# Motor_Driver_Unit_MDU.net
KiCad netlist of a schematic drawn in Altium Designer
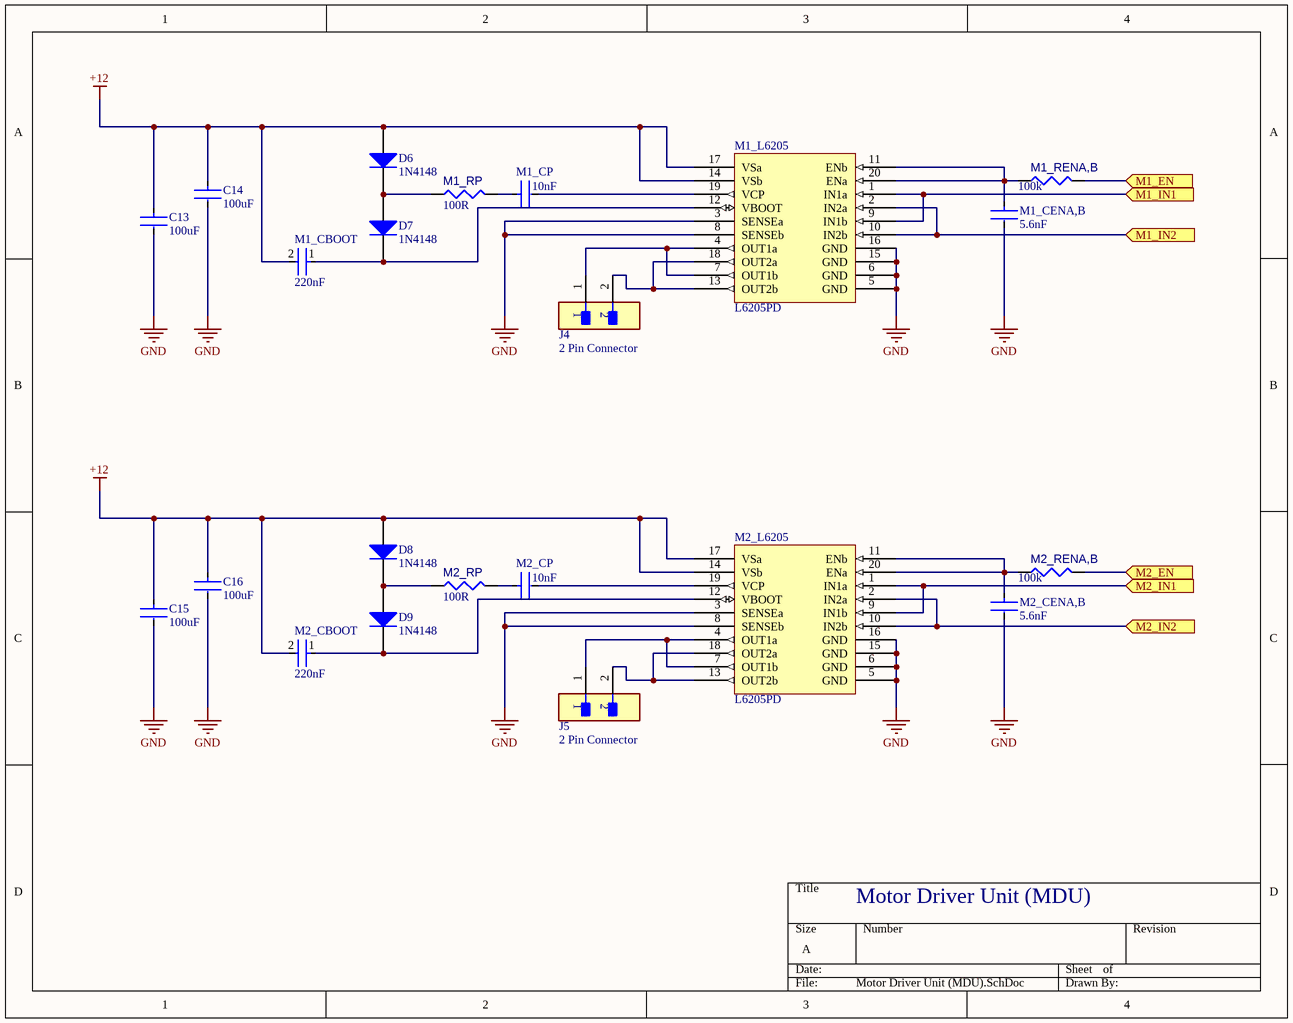
[diagram p0: Motor Driver Unit (MDU).SchDoc]

(export (version "E")
  (design (tool "Eeschema 10.0.6"))
  (components
    (comp (ref "C13")
      (value "100uF")
      (footprint "FP-C3216-160-0_3-IPC_C")
      (description "Multilayer Ceramic Capacitors 100uF ±20% 10V X5R SMD 1206")
      (fields (field (name "VOLTAGE") "10V") (field (name "TOLERANCE") "20%"))
      (libsource (lib "Altium Content Vault") (part "02cd4be3c70576c341d710602a673aa"))
    )
    (comp (ref "C14")
      (value "100uF")
      (footprint "FP-C3216-160-0_3-IPC_C")
      (description "Multilayer Ceramic Capacitors 100uF ±20% 10V X5R SMD 1206")
      (fields (field (name "VOLTAGE") "10V") (field (name "TOLERANCE") "20%"))
      (libsource (lib "Altium Content Vault") (part "02cd4be3c70576c341d710602a673aa"))
    )
    (comp (ref "C15")
      (value "100uF")
      (footprint "FP-C3216-160-0_3-IPC_C")
      (description "Multilayer Ceramic Capacitors 100uF ±20% 10V X5R SMD 1206")
      (fields (field (name "VOLTAGE") "10V") (field (name "TOLERANCE") "20%"))
      (libsource (lib "Altium Content Vault") (part "02cd4be3c70576c341d710602a673aa"))
    )
    (comp (ref "C16")
      (value "100uF")
      (footprint "FP-C3216-160-0_3-IPC_C")
      (description "Multilayer Ceramic Capacitors 100uF ±20% 10V X5R SMD 1206")
      (fields (field (name "VOLTAGE") "10V") (field (name "TOLERANCE") "20%"))
      (libsource (lib "Altium Content Vault") (part "02cd4be3c70576c341d710602a673aa"))
    )
    (comp (ref "D6")
      (value "1N4148")
      (footprint "NXP-SOD27-2_V")
      (description "High Speed Diode, 100 V, 0.45 A, -65 to 175 degC, 2-Pin SOD27, RoHS, Bulk")
      (fields (field (name "POWER") "500mW") (field (name "MANUFACTURER") "Fairchild"))
      (libsource (lib "University of Salford") (part "D-AK-2"))
    )
    (comp (ref "D7")
      (value "1N4148")
      (footprint "NXP-SOD27-2_V")
      (description "High Speed Diode, 100 V, 0.45 A, -65 to 175 degC, 2-Pin SOD27, RoHS, Bulk")
      (fields (field (name "POWER") "500mW") (field (name "MANUFACTURER") "Fairchild"))
      (libsource (lib "University of Salford") (part "D-AK-2"))
    )
    (comp (ref "D8")
      (value "1N4148")
      (footprint "NXP-SOD27-2_V")
      (description "High Speed Diode, 100 V, 0.45 A, -65 to 175 degC, 2-Pin SOD27, RoHS, Bulk")
      (fields (field (name "POWER") "500mW") (field (name "MANUFACTURER") "Fairchild"))
      (libsource (lib "University of Salford") (part "D-AK-2"))
    )
    (comp (ref "D9")
      (value "1N4148")
      (footprint "NXP-SOD27-2_V")
      (description "High Speed Diode, 100 V, 0.45 A, -65 to 175 degC, 2-Pin SOD27, RoHS, Bulk")
      (fields (field (name "POWER") "500mW") (field (name "MANUFACTURER") "Fairchild"))
      (libsource (lib "University of Salford") (part "D-AK-2"))
    )
    (comp (ref "J4")
      (value "2 Pin Connector")
      (footprint "FP-53048-0210-MFG")
      (description "CONN HEADER R/A 2POS 1.25MM")
      (libsource (lib "Altium Content Vault") (part "88c1139f9d239099ffebecbe3f7647a"))
    )
    (comp (ref "J5")
      (value "2 Pin Connector")
      (footprint "FP-53048-0210-MFG")
      (description "CONN HEADER R/A 2POS 1.25MM")
      (libsource (lib "Altium Content Vault") (part "88c1139f9d239099ffebecbe3f7647a"))
    )
    (comp (ref "M1_CBOOT")
      (value "220nF")
      (footprint "FP-CL21-IPC_C")
      (description "CL21 Series 0805 220nF 25V ±10% Tolerance X7R Multilayer Ceramic Chip Capacitor")
      (fields (field (name "TOLERANCE") "10%"))
      (libsource (lib "Altium Content Vault") (part "b4654b650e69147ec39a6b967a45e02"))
    )
    (comp (ref "M1_CENA,B")
      (value "5.6nF")
      (footprint "FP-CC0603-DA-MFG")
      (description "Surface Mount Ceramic Multilayer Capacitor 0.0056uF 10% X7R 50V 0603 Paper T/R")
      (fields
        (field (name "MANUFACTURER PART NUMBER") "CC0603KRX7R9BB562")
        (field (name "MANUFACTURER") "YAGEO")
      )
      (libsource (lib "Altium Content Vault") (part "11868f565c42a9108669ba33697ecf6"))
    )
    (comp (ref "M1_CP")
      (value "10nF")
      (footprint "FP-CC0402-MFG")
      (description "CAP CER 10000PF 50V X7R 0402")
      (fields
        (field (name "OCTOPART") "https://octopart.com/cc0402krx7r9bb103-yageo-8376513")
        (field (name "MANUFACTURER PART NUMBER") "CC0402KRX7R9BB103")
      )
      (libsource (lib "Altium Content Vault") (part "11868f565c42a9108669ba33697ecf6"))
    )
    (comp (ref "M1_L6205")
      (value "L6205PD")
      (footprint "SOJ127P870X356-20M")
      (description "Stepper Motor Controller, 5.6A, BCDMOS, PDSO20")
      (libsource (lib "University of Salford") (part "L6205PD-Symbol-1"))
    )
    (comp (ref "M1_RENA,B")
      (value "100k")
      (footprint "RESC1005X40X25ML05T05")
      (description "Chip Resistor, 100 KOhm, +/- 1%, 0.1 W, -55 to 155 degC, 0402 (1005 Metric)")
      (fields (field (name "POWER") "100mW") (field (name "TOLERANCE") "1%"))
      (libsource (lib "University of Salford") (part "RES-2"))
    )
    (comp (ref "M1_RP")
      (value "100R")
      (footprint "RESC0402(1005)_L")
      (description "100R 0.063W 1% 0402 (1005 Metric)  SMD")
      (fields (field (name "TOLERANCE") "1%") (field (name "POWER") "63mW"))
      (libsource (lib "University of Salford") (part "100R2F"))
    )
    (comp (ref "M2_CBOOT")
      (value "220nF")
      (footprint "FP-CL21-IPC_C")
      (description "CL21 Series 0805 220nF 25V ±10% Tolerance X7R Multilayer Ceramic Chip Capacitor")
      (fields (field (name "TOLERANCE") "10%"))
      (libsource (lib "Altium Content Vault") (part "b4654b650e69147ec39a6b967a45e02"))
    )
    (comp (ref "M2_CENA,B")
      (value "5.6nF")
      (footprint "FP-CC0603-DA-MFG")
      (description "Surface Mount Ceramic Multilayer Capacitor 0.0056uF 10% X7R 50V 0603 Paper T/R")
      (fields
        (field (name "MANUFACTURER PART NUMBER") "CC0603KRX7R9BB562")
        (field (name "MANUFACTURER") "YAGEO")
      )
      (libsource (lib "Altium Content Vault") (part "11868f565c42a9108669ba33697ecf6"))
    )
    (comp (ref "M2_CP")
      (value "10nF")
      (footprint "FP-CC0402-MFG")
      (description "CAP CER 10000PF 50V X7R 0402")
      (fields
        (field (name "OCTOPART") "https://octopart.com/cc0402krx7r9bb103-yageo-8376513")
        (field (name "MANUFACTURER PART NUMBER") "CC0402KRX7R9BB103")
      )
      (libsource (lib "Altium Content Vault") (part "11868f565c42a9108669ba33697ecf6"))
    )
    (comp (ref "M2_L6205")
      (value "L6205PD")
      (footprint "SOJ127P870X356-20M")
      (description "Stepper Motor Controller, 5.6A, BCDMOS, PDSO20")
      (libsource (lib "University of Salford") (part "L6205PD-Symbol-1"))
    )
    (comp (ref "M2_RENA,B")
      (value "100k")
      (footprint "RESC1005X40X25ML05T05")
      (description "Chip Resistor, 100 KOhm, +/- 1%, 0.1 W, -55 to 155 degC, 0402 (1005 Metric)")
      (fields (field (name "POWER") "100mW") (field (name "TOLERANCE") "1%"))
      (libsource (lib "University of Salford") (part "RES-2"))
    )
    (comp (ref "M2_RP")
      (value "100R")
      (footprint "RESC0402(1005)_L")
      (description "100R 0.063W 1% 0402 (1005 Metric)  SMD")
      (fields (field (name "TOLERANCE") "1%") (field (name "POWER") "63mW"))
      (libsource (lib "University of Salford") (part "100R2F"))
    )
  )
  (nets
    (net (code "1") (name "+12") (class "Default")
      (node (ref "C13") (pin "1") (pinfunction "1_1") (pintype "passive"))
      (node (ref "C14") (pin "1") (pinfunction "1_1") (pintype "passive"))
      (node (ref "C15") (pin "1") (pinfunction "1_1") (pintype "passive"))
      (node (ref "C16") (pin "1") (pinfunction "1_1") (pintype "passive"))
      (node (ref "D6") (pin "1") (pinfunction "A_1") (pintype "passive"))
      (node (ref "D8") (pin "1") (pinfunction "A_1") (pintype "passive"))
      (node (ref "M1_CBOOT") (pin "2") (pinfunction "2_2") (pintype "passive"))
      (node (ref "M1_L6205") (pin "14") (pinfunction "VSb_14") (pintype "power_in"))
      (node (ref "M1_L6205") (pin "17") (pinfunction "VSa_17") (pintype "power_in"))
      (node (ref "M2_CBOOT") (pin "2") (pinfunction "2_2") (pintype "passive"))
      (node (ref "M2_L6205") (pin "14") (pinfunction "VSb_14") (pintype "power_in"))
      (node (ref "M2_L6205") (pin "17") (pinfunction "VSa_17") (pintype "power_in"))
    )
    (net (code "2") (name "/M1_EN") (class "Default")
      (node (ref "M1_RENA,B") (pin "2") (pinfunction "2_2") (pintype "passive"))
    )
    (net (code "3") (name "/M1_IN1") (class "Default")
      (node (ref "M1_L6205") (pin "1") (pinfunction "IN1a_1") (pintype "input"))
      (node (ref "M1_L6205") (pin "9") (pinfunction "IN1b_9") (pintype "input"))
    )
    (net (code "4") (name "/M1_IN2") (class "Default")
      (node (ref "M1_L6205") (pin "10") (pinfunction "IN2b_10") (pintype "input"))
      (node (ref "M1_L6205") (pin "2") (pinfunction "IN2a_2") (pintype "input"))
    )
    (net (code "5") (name "/M2_EN") (class "Default")
      (node (ref "M2_RENA,B") (pin "2") (pinfunction "2_2") (pintype "passive"))
    )
    (net (code "6") (name "/M2_IN1") (class "Default")
      (node (ref "M2_L6205") (pin "1") (pinfunction "IN1a_1") (pintype "input"))
      (node (ref "M2_L6205") (pin "9") (pinfunction "IN1b_9") (pintype "input"))
    )
    (net (code "7") (name "/M2_IN2") (class "Default")
      (node (ref "M2_L6205") (pin "10") (pinfunction "IN2b_10") (pintype "input"))
      (node (ref "M2_L6205") (pin "2") (pinfunction "IN2a_2") (pintype "input"))
    )
    (net (code "8") (name "GND") (class "Default")
      (node (ref "C13") (pin "2") (pinfunction "2_2") (pintype "passive"))
      (node (ref "C14") (pin "2") (pinfunction "2_2") (pintype "passive"))
      (node (ref "C15") (pin "2") (pinfunction "2_2") (pintype "passive"))
      (node (ref "C16") (pin "2") (pinfunction "2_2") (pintype "passive"))
      (node (ref "M1_CENA,B") (pin "2") (pinfunction "2_2") (pintype "passive"))
      (node (ref "M1_L6205") (pin "15") (pinfunction "GND_15") (pintype "power_in"))
      (node (ref "M1_L6205") (pin "16") (pinfunction "GND_16") (pintype "power_in"))
      (node (ref "M1_L6205") (pin "3") (pinfunction "SENSEa_3") (pintype "passive"))
      (node (ref "M1_L6205") (pin "5") (pinfunction "GND_5") (pintype "power_in"))
      (node (ref "M1_L6205") (pin "6") (pinfunction "GND_6") (pintype "power_in"))
      (node (ref "M1_L6205") (pin "8") (pinfunction "SENSEb_8") (pintype "passive"))
      (node (ref "M2_CENA,B") (pin "2") (pinfunction "2_2") (pintype "passive"))
      (node (ref "M2_L6205") (pin "15") (pinfunction "GND_15") (pintype "power_in"))
      (node (ref "M2_L6205") (pin "16") (pinfunction "GND_16") (pintype "power_in"))
      (node (ref "M2_L6205") (pin "3") (pinfunction "SENSEa_3") (pintype "passive"))
      (node (ref "M2_L6205") (pin "5") (pinfunction "GND_5") (pintype "power_in"))
      (node (ref "M2_L6205") (pin "6") (pinfunction "GND_6") (pintype "power_in"))
      (node (ref "M2_L6205") (pin "8") (pinfunction "SENSEb_8") (pintype "passive"))
    )
    (net (code "9") (name "Net-(D6-K)") (class "Default")
      (node (ref "D6") (pin "2") (pinfunction "K_2") (pintype "passive"))
      (node (ref "D7") (pin "1") (pinfunction "A_1") (pintype "passive"))
      (node (ref "M1_RP") (pin "1") (pinfunction "1_1") (pintype "passive"))
    )
    (net (code "10") (name "Net-(D7-K)") (class "Default")
      (node (ref "D7") (pin "2") (pinfunction "K_2") (pintype "passive"))
      (node (ref "M1_CBOOT") (pin "1") (pinfunction "1_1") (pintype "passive"))
      (node (ref "M1_L6205") (pin "12") (pinfunction "VBOOT_12") (pintype "bidirectional"))
    )
    (net (code "11") (name "Net-(D8-K)") (class "Default")
      (node (ref "D8") (pin "2") (pinfunction "K_2") (pintype "passive"))
      (node (ref "D9") (pin "1") (pinfunction "A_1") (pintype "passive"))
      (node (ref "M2_RP") (pin "1") (pinfunction "1_1") (pintype "passive"))
    )
    (net (code "12") (name "Net-(D9-K)") (class "Default")
      (node (ref "D9") (pin "2") (pinfunction "K_2") (pintype "passive"))
      (node (ref "M2_CBOOT") (pin "1") (pinfunction "1_1") (pintype "passive"))
      (node (ref "M2_L6205") (pin "12") (pinfunction "VBOOT_12") (pintype "bidirectional"))
    )
    (net (code "13") (name "Net-(M1_CP-Pad1)") (class "Default")
      (node (ref "M1_CP") (pin "1") (pinfunction "1_1") (pintype "passive"))
      (node (ref "M1_RP") (pin "2") (pinfunction "2_2") (pintype "passive"))
    )
    (net (code "14") (name "Net-(M1_L6205-ENa)") (class "Default")
      (node (ref "M1_CENA,B") (pin "1") (pinfunction "1_1") (pintype "passive"))
      (node (ref "M1_L6205") (pin "11") (pinfunction "ENb_11") (pintype "input"))
      (node (ref "M1_L6205") (pin "20") (pinfunction "ENa_20") (pintype "input"))
      (node (ref "M1_RENA,B") (pin "1") (pinfunction "1_1") (pintype "passive"))
    )
    (net (code "15") (name "Net-(M1_L6205-OUT1a)") (class "Default")
      (node (ref "J4") (pin "1") (pinfunction "1_1") (pintype "passive"))
      (node (ref "M1_L6205") (pin "4") (pinfunction "OUT1a_4") (pintype "output"))
      (node (ref "M1_L6205") (pin "7") (pinfunction "OUT1b_7") (pintype "output"))
    )
    (net (code "16") (name "Net-(M1_L6205-OUT2a)") (class "Default")
      (node (ref "J4") (pin "2") (pinfunction "2_2") (pintype "passive"))
      (node (ref "M1_L6205") (pin "13") (pinfunction "OUT2b_13") (pintype "output"))
      (node (ref "M1_L6205") (pin "18") (pinfunction "OUT2a_18") (pintype "output"))
    )
    (net (code "17") (name "Net-(M1_L6205-VCP)") (class "Default")
      (node (ref "M1_CP") (pin "2") (pinfunction "2_2") (pintype "passive"))
      (node (ref "M1_L6205") (pin "19") (pinfunction "VCP_19") (pintype "output"))
    )
    (net (code "18") (name "Net-(M2_CP-Pad1)") (class "Default")
      (node (ref "M2_CP") (pin "1") (pinfunction "1_1") (pintype "passive"))
      (node (ref "M2_RP") (pin "2") (pinfunction "2_2") (pintype "passive"))
    )
    (net (code "19") (name "Net-(M2_L6205-ENa)") (class "Default")
      (node (ref "M2_CENA,B") (pin "1") (pinfunction "1_1") (pintype "passive"))
      (node (ref "M2_L6205") (pin "11") (pinfunction "ENb_11") (pintype "input"))
      (node (ref "M2_L6205") (pin "20") (pinfunction "ENa_20") (pintype "input"))
      (node (ref "M2_RENA,B") (pin "1") (pinfunction "1_1") (pintype "passive"))
    )
    (net (code "20") (name "Net-(M2_L6205-OUT1a)") (class "Default")
      (node (ref "J5") (pin "1") (pinfunction "1_1") (pintype "passive"))
      (node (ref "M2_L6205") (pin "4") (pinfunction "OUT1a_4") (pintype "output"))
      (node (ref "M2_L6205") (pin "7") (pinfunction "OUT1b_7") (pintype "output"))
    )
    (net (code "21") (name "Net-(M2_L6205-OUT2a)") (class "Default")
      (node (ref "J5") (pin "2") (pinfunction "2_2") (pintype "passive"))
      (node (ref "M2_L6205") (pin "13") (pinfunction "OUT2b_13") (pintype "output"))
      (node (ref "M2_L6205") (pin "18") (pinfunction "OUT2a_18") (pintype "output"))
    )
    (net (code "22") (name "Net-(M2_L6205-VCP)") (class "Default")
      (node (ref "M2_CP") (pin "2") (pinfunction "2_2") (pintype "passive"))
      (node (ref "M2_L6205") (pin "19") (pinfunction "VCP_19") (pintype "output"))
    )
  )
)
